# EPS_Local-Supply.net
KiCad netlist of a schematic drawn in Altium Designer
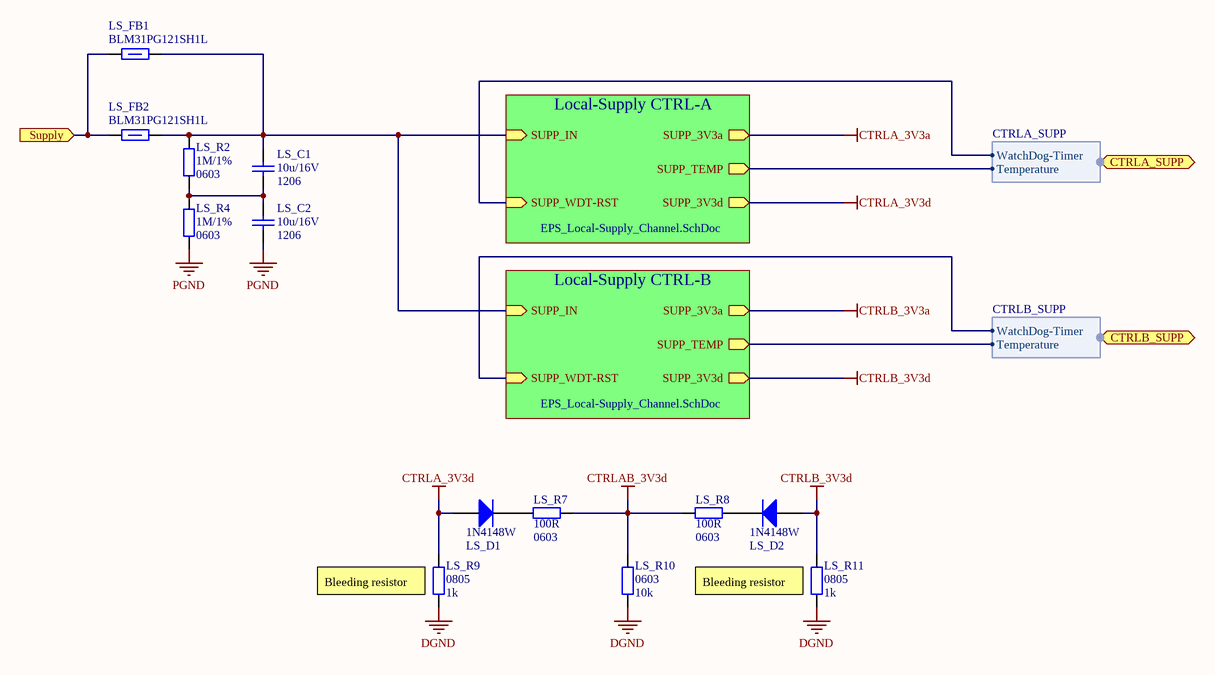
[diagram p0: EPS_Local-Supply.SchDoc]

(export (version "E")
  (design (tool "Eeschema 10.0.6"))
  (components
    (comp (ref "LS_C1")
      (value "10u/16V")
      (footprint "SMD_Capacitor_1206")
      (description "Ceramic Cap Kemet COTS 10u/16V X7R 1206")
      (fields
        (field (name "MANUFACTURERPARTNUMBER") "C1206T106K4RACTU")
        (field (name "MANUFACTURER") "Kemet")
        (field (name "PACKGE") "1206")
      )
      (libsource (lib "capacitors") (part "Cer_C1206T106K4RACTU"))
    )
    (comp (ref "LS_C2")
      (value "10u/16V")
      (footprint "SMD_Capacitor_1206")
      (description "Ceramic Cap Kemet COTS 10u/16V X7R 1206")
      (fields
        (field (name "MANUFACTURERPARTNUMBER") "C1206T106K4RACTU")
        (field (name "MANUFACTURER") "Kemet")
        (field (name "PACKGE") "1206")
      )
      (libsource (lib "capacitors") (part "Cer_C1206T106K4RACTU"))
    )
    (comp (ref "LS_D1")
      (value "1N4148W")
      (footprint "SOD-123")
      (description "Small Signal Fast Switching Diode")
      (fields (field (name "MANUFACTURER") "Vishay"))
      (libsource (lib "diodes") (part "1N4148W"))
    )
    (comp (ref "LS_D2")
      (value "1N4148W")
      (footprint "SOD-123")
      (description "Small Signal Fast Switching Diode")
      (fields (field (name "MANUFACTURER") "Vishay"))
      (libsource (lib "diodes") (part "1N4148W"))
    )
    (comp (ref "LS_FB1")
      (value "120R/100MHz")
      (footprint "SMD_FerriteBead_1206")
      (description "Ferrite bead, 1206, 0.02HM, 3.5A.")
      (fields (field (name "MANUFACTURER") "Murata") (field (name "MANUFACTURERPARTNUMBER") "BLM31PG121SH1L"))
      (libsource (lib "inductors") (part "BLM31PG121SH1L"))
    )
    (comp (ref "LS_FB2")
      (value "120R/100MHz")
      (footprint "SMD_FerriteBead_1206")
      (description "Ferrite bead, 1206, 0.02HM, 3.5A.")
      (fields (field (name "MANUFACTURER") "Murata") (field (name "MANUFACTURERPARTNUMBER") "BLM31PG121SH1L"))
      (libsource (lib "inductors") (part "BLM31PG121SH1L"))
    )
    (comp (ref "LS_R2")
      (value "1M/1%")
      (footprint "SMD_Resistor_0603")
      (fields (field (name "PACKAGE") "0603"))
      (libsource (lib "") (part "Res_1"))
    )
    (comp (ref "LS_R4")
      (value "1M/1%")
      (footprint "SMD_Resistor_0603")
      (fields (field (name "PACKAGE") "0603"))
      (libsource (lib "") (part "Res_1"))
    )
    (comp (ref "LS_R7")
      (value "100R")
      (footprint "SMD_Resistor_0603")
      (fields (field (name "PACKAGE") "0603"))
      (libsource (lib "resistors") (part "Res"))
    )
    (comp (ref "LS_R8")
      (value "100R")
      (footprint "SMD_Resistor_0603")
      (fields (field (name "PACKAGE") "0603"))
      (libsource (lib "resistors") (part "Res"))
    )
    (comp (ref "LS_R9")
      (value "1k")
      (footprint "SMD_Resistor_0805")
      (fields (field (name "PACKAGE") "0805"))
      (libsource (lib "resistors") (part "Res"))
    )
    (comp (ref "LS_R10")
      (value "10k")
      (footprint "SMD_Resistor_0603")
      (fields (field (name "PACKAGE") "0603"))
      (libsource (lib "resistors") (part "Res"))
    )
    (comp (ref "LS_R11")
      (value "1k")
      (footprint "SMD_Resistor_0805")
      (fields (field (name "PACKAGE") "0805"))
      (libsource (lib "resistors") (part "Res"))
    )
  )
  (nets
    (net (code "3") (name "/SUPP_IN") (class "Default")
      (node (ref "LS_C1") (pin "1") (pinfunction "1_1") (pintype "passive"))
      (node (ref "LS_FB1") (pin "2") (pinfunction "2_2") (pintype "passive"))
      (node (ref "LS_FB2") (pin "2") (pinfunction "2_2") (pintype "passive"))
      (node (ref "LS_R2") (pin "1") (pinfunction "1_1") (pintype "passive"))
    )
    (net (code "8") (name "/Supply") (class "Default")
      (node (ref "LS_FB1") (pin "1") (pinfunction "1_1") (pintype "passive"))
      (node (ref "LS_FB2") (pin "1") (pinfunction "1_1") (pintype "passive"))
    )
    (net (code "11") (name "CTRLAB_3V3d") (class "Default")
      (node (ref "LS_R10") (pin "2") (pinfunction "2_2") (pintype "passive"))
      (node (ref "LS_R7") (pin "2") (pinfunction "2_2") (pintype "passive"))
      (node (ref "LS_R8") (pin "1") (pinfunction "1_1") (pintype "passive"))
    )
    (net (code "13") (name "CTRLA_3V3d") (class "Default")
      (node (ref "LS_D1") (pin "A") (pinfunction "A_A") (pintype "passive"))
      (node (ref "LS_R9") (pin "2") (pinfunction "2_2") (pintype "passive"))
    )
    (net (code "15") (name "CTRLB_3V3d") (class "Default")
      (node (ref "LS_D2") (pin "A") (pinfunction "A_A") (pintype "passive"))
      (node (ref "LS_R11") (pin "2") (pinfunction "2_2") (pintype "passive"))
    )
    (net (code "16") (name "DGND") (class "Default")
      (node (ref "LS_R10") (pin "1") (pinfunction "1_1") (pintype "passive"))
      (node (ref "LS_R11") (pin "1") (pinfunction "1_1") (pintype "passive"))
      (node (ref "LS_R9") (pin "1") (pinfunction "1_1") (pintype "passive"))
    )
    (net (code "17") (name "Net-(LS_C1-Pad2)") (class "Default")
      (node (ref "LS_C1") (pin "2") (pinfunction "2_2") (pintype "passive"))
      (node (ref "LS_C2") (pin "1") (pinfunction "1_1") (pintype "passive"))
      (node (ref "LS_R2") (pin "2") (pinfunction "2_2") (pintype "passive"))
      (node (ref "LS_R4") (pin "1") (pinfunction "1_1") (pintype "passive"))
    )
    (net (code "18") (name "Net-(LS_D1-PadK)") (class "Default")
      (node (ref "LS_D1") (pin "K") (pinfunction "K_K") (pintype "passive"))
      (node (ref "LS_R7") (pin "1") (pinfunction "1_1") (pintype "passive"))
    )
    (net (code "19") (name "Net-(LS_D2-PadK)") (class "Default")
      (node (ref "LS_D2") (pin "K") (pinfunction "K_K") (pintype "passive"))
      (node (ref "LS_R8") (pin "2") (pinfunction "2_2") (pintype "passive"))
    )
    (net (code "20") (name "PGND") (class "Default")
      (node (ref "LS_C2") (pin "2") (pinfunction "2_2") (pintype "passive"))
      (node (ref "LS_R4") (pin "2") (pinfunction "2_2") (pintype "passive"))
    )
  )
)
